# w47_LED_RGB_pinout.net
KiCad netlist of a schematic drawn in Altium Designer
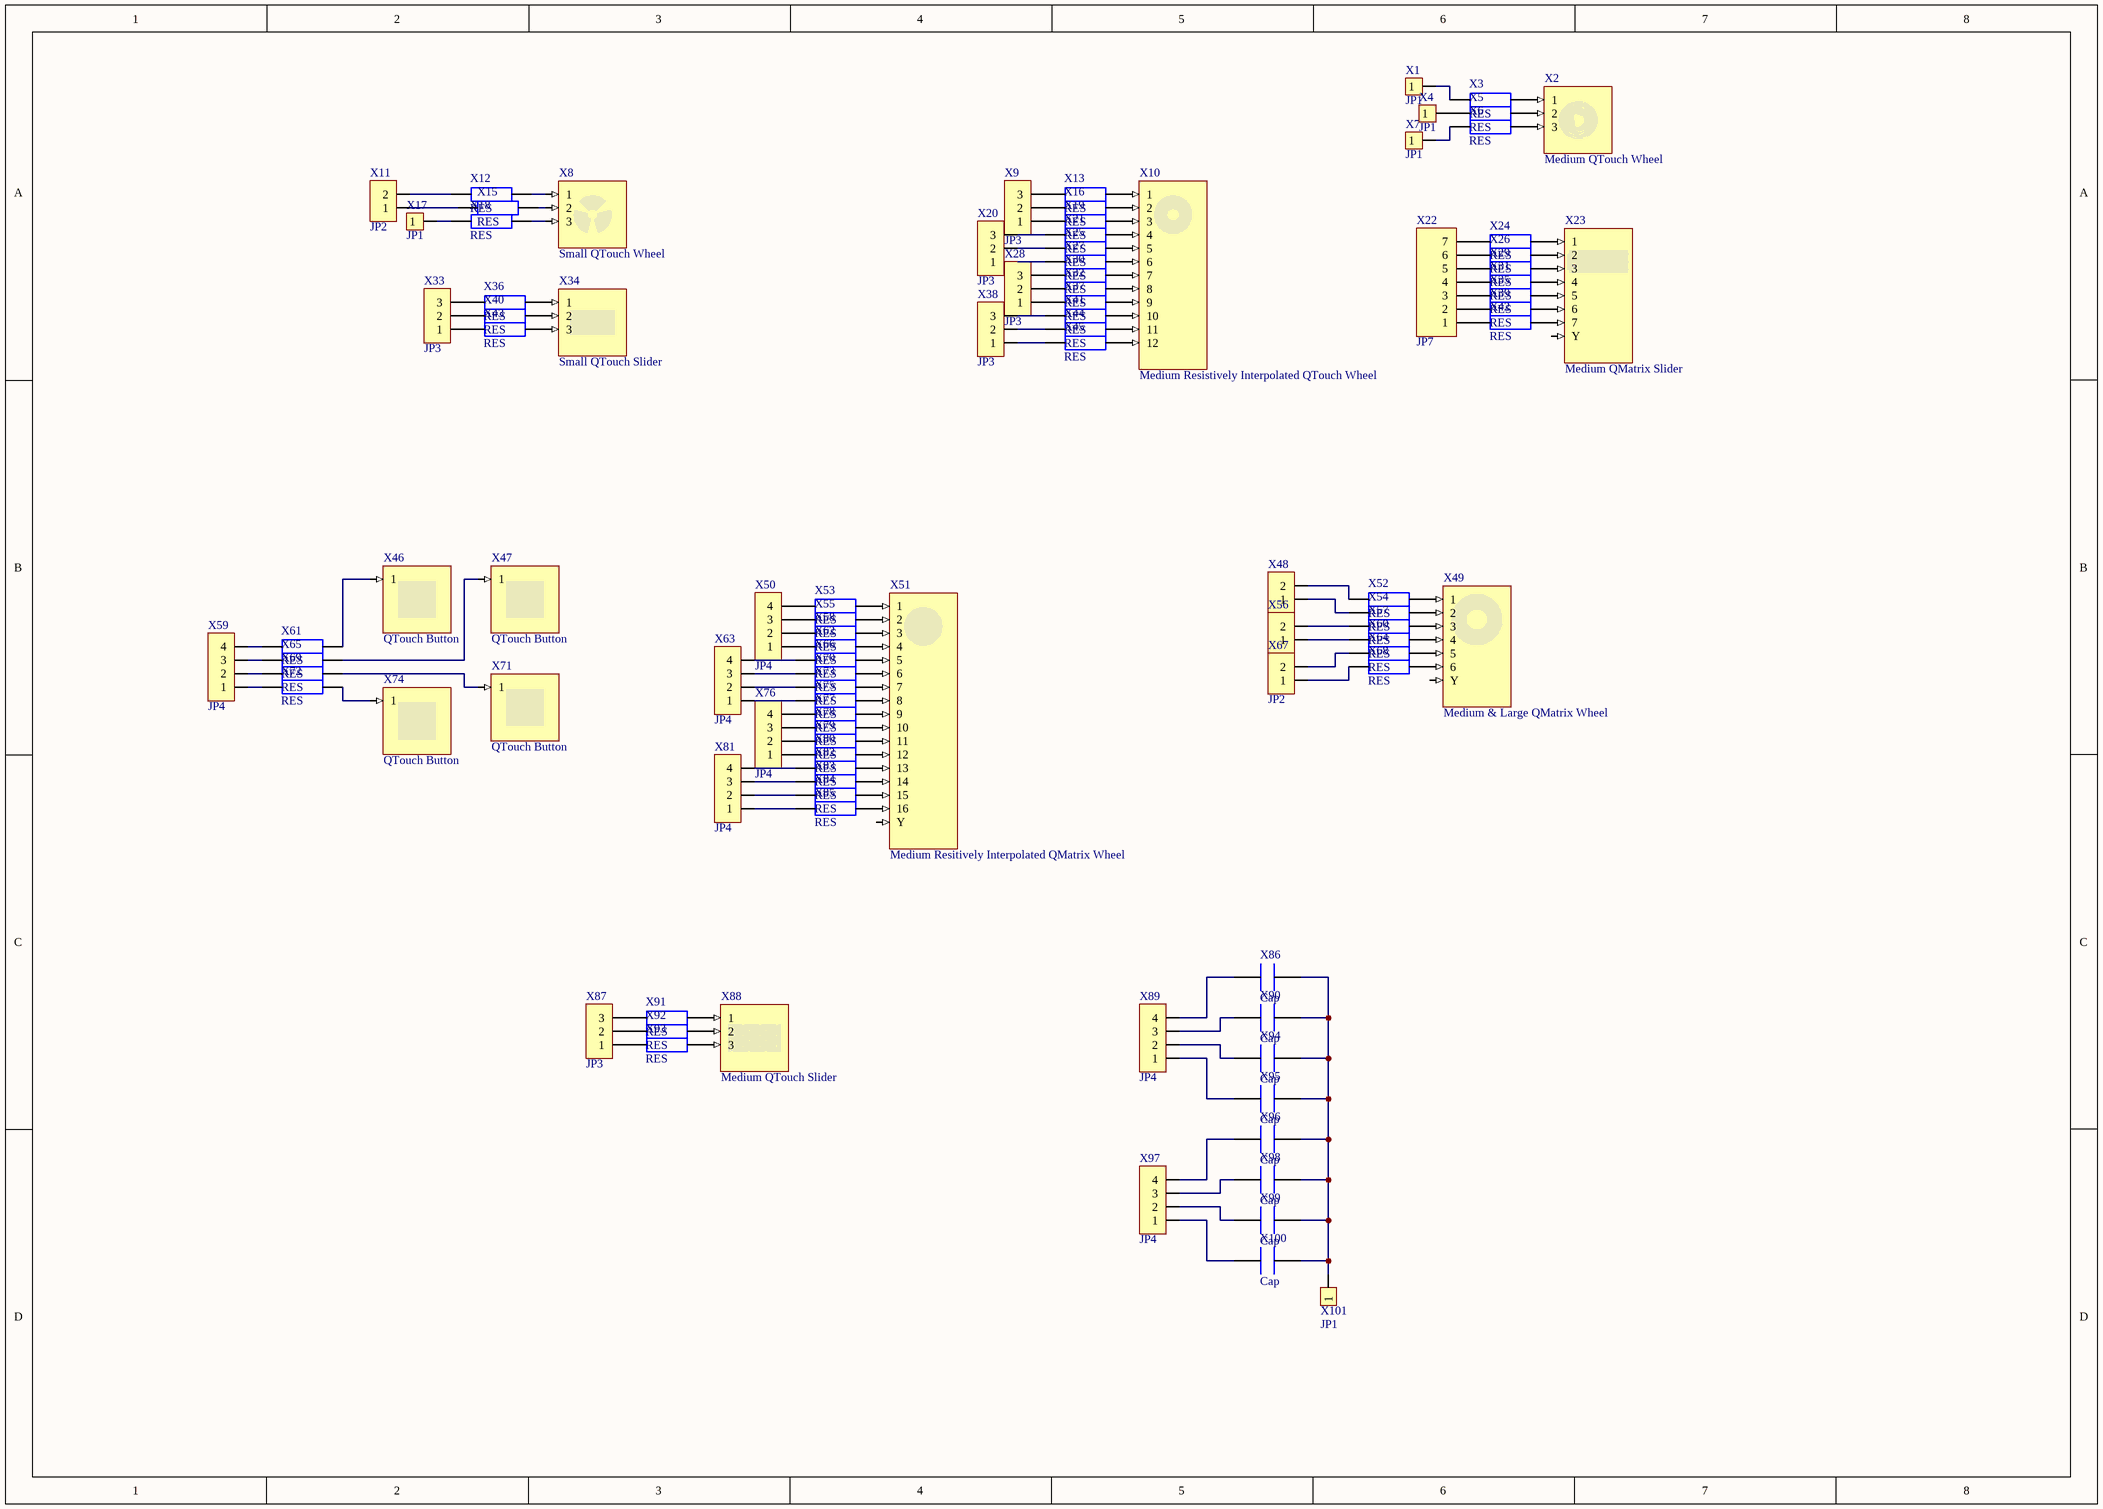
[diagram p0: w47_LED_RGB_pinout.SchDoc]

(export (version "E")
  (design (tool "Eeschema 10.0.6"))
  (components
    (comp (ref "X1")
      (value "JP1")
      (footprint "JP1-D1T")
      (description "WR-PHD 2.54 mm Angled Socket Header")
      (fields
        (field (name "MANUFACTURER") "Würth Elektronik eiSos GmbH")
        (field (name "PARTNO") "613002143121")
        (field (name "CREATED BY") "Karrer Zheng")
      )
      (libsource (lib "LIBRARY") (part "JP1"))
    )
    (comp (ref "X2")
      (value "Medium QTouch Wheel")
      (libsource (lib "Atmel QTouch") (part "MediumQTouchWheel"))
    )
    (comp (ref "X3")
      (value "RES")
      (footprint "RES")
      (description "điện trở size nhỏ")
      (libsource (lib "LuongTanDat") (part "RES"))
    )
    (comp (ref "X4")
      (value "JP1")
      (footprint "JP1-D1T")
      (description "WR-PHD 2.54 mm Angled Socket Header")
      (fields
        (field (name "MANUFACTURER") "Würth Elektronik eiSos GmbH")
        (field (name "PARTNO") "613002143121")
        (field (name "CREATED BY") "Karrer Zheng")
      )
      (libsource (lib "LIBRARY") (part "JP1"))
    )
    (comp (ref "X5")
      (value "RES")
      (footprint "RES")
      (description "điện trở size nhỏ")
      (libsource (lib "LuongTanDat") (part "RES"))
    )
    (comp (ref "X6")
      (value "RES")
      (footprint "RES")
      (description "điện trở size nhỏ")
      (libsource (lib "LuongTanDat") (part "RES"))
    )
    (comp (ref "X7")
      (value "JP1")
      (footprint "JP1-D1T")
      (description "WR-PHD 2.54 mm Angled Socket Header")
      (fields
        (field (name "MANUFACTURER") "Würth Elektronik eiSos GmbH")
        (field (name "PARTNO") "613002143121")
        (field (name "CREATED BY") "Karrer Zheng")
      )
      (libsource (lib "LIBRARY") (part "JP1"))
    )
    (comp (ref "X8") (value "Small QTouch Wheel") (libsource (lib "Atmel QTouch") (part "SmallQTouchWheel")))
    (comp (ref "X9")
      (value "JP3")
      (footprint "JP3-C1T")
      (description "WR-PHD 2.54 mm Angled Socket Header")
      (fields
        (field (name "MANUFACTURER") "Würth Elektronik eiSos GmbH")
        (field (name "PARTNO") "613003143121")
        (field (name "CREATED BY") "Karrer Zheng")
      )
      (libsource (lib "LIBRARY") (part "JP3"))
    )
    (comp (ref "X10")
      (value "Medium Resistively Interpolated QTouch Wheel")
      (libsource (lib "Atmel QTouch") (part "MediumResQTouchWheel"))
    )
    (comp (ref "X11")
      (value "JP2")
      (footprint "JP2-C1T")
      (description "WR-PHD 2.54 mm Angled Socket Header")
      (fields
        (field (name "MANUFACTURER") "Würth Elektronik eiSos GmbH")
        (field (name "PARTNO") "613002143121")
        (field (name "CREATED BY") "Karrer Zheng")
      )
      (libsource (lib "LIBRARY") (part "JP2"))
    )
    (comp (ref "X12")
      (value "RES")
      (footprint "RES")
      (description "điện trở size nhỏ")
      (libsource (lib "LuongTanDat") (part "RES"))
    )
    (comp (ref "X13")
      (value "RES")
      (footprint "RES")
      (description "điện trở size nhỏ")
      (libsource (lib "LuongTanDat") (part "RES"))
    )
    (comp (ref "X15")
      (value "RES")
      (footprint "RES")
      (description "điện trở size nhỏ")
      (libsource (lib "LuongTanDat") (part "RES"))
    )
    (comp (ref "X16")
      (value "RES")
      (footprint "RES")
      (description "điện trở size nhỏ")
      (libsource (lib "LuongTanDat") (part "RES"))
    )
    (comp (ref "X17")
      (value "JP1")
      (footprint "JP1-D1T")
      (description "WR-PHD 2.54 mm Angled Socket Header")
      (fields
        (field (name "MANUFACTURER") "Würth Elektronik eiSos GmbH")
        (field (name "PARTNO") "613002143121")
        (field (name "CREATED BY") "Karrer Zheng")
      )
      (libsource (lib "LIBRARY") (part "JP1"))
    )
    (comp (ref "X18")
      (value "RES")
      (footprint "RES")
      (description "điện trở size nhỏ")
      (libsource (lib "LuongTanDat") (part "RES"))
    )
    (comp (ref "X19")
      (value "RES")
      (footprint "RES")
      (description "điện trở size nhỏ")
      (libsource (lib "LuongTanDat") (part "RES"))
    )
    (comp (ref "X20")
      (value "JP3")
      (footprint "JP3-C1T")
      (description "WR-PHD 2.54 mm Angled Socket Header")
      (fields
        (field (name "MANUFACTURER") "Würth Elektronik eiSos GmbH")
        (field (name "PARTNO") "613003143121")
        (field (name "CREATED BY") "Karrer Zheng")
      )
      (libsource (lib "LIBRARY") (part "JP3"))
    )
    (comp (ref "X21")
      (value "RES")
      (footprint "RES")
      (description "điện trở size nhỏ")
      (libsource (lib "LuongTanDat") (part "RES"))
    )
    (comp (ref "X22")
      (value "JP7")
      (footprint "JP7-D1T")
      (description "WR-PHD 2.54 mm Angled Socket Header")
      (fields
        (field (name "MANUFACTURER") "Würth Elektronik eiSos GmbH")
        (field (name "PARTNO") "613007143121")
        (field (name "CREATED BY") "Karrer Zheng")
      )
      (libsource (lib "LIBRARY") (part "JP7"))
    )
    (comp (ref "X23")
      (value "Medium QMatrix Slider")
      (libsource (lib "Atmel QTouch") (part "MediumQMatrixSlider"))
    )
    (comp (ref "X24")
      (value "RES")
      (footprint "RES")
      (description "điện trở size nhỏ")
      (libsource (lib "LuongTanDat") (part "RES"))
    )
    (comp (ref "X25")
      (value "RES")
      (footprint "RES")
      (description "điện trở size nhỏ")
      (libsource (lib "LuongTanDat") (part "RES"))
    )
    (comp (ref "X26")
      (value "RES")
      (footprint "RES")
      (description "điện trở size nhỏ")
      (libsource (lib "LuongTanDat") (part "RES"))
    )
    (comp (ref "X27")
      (value "RES")
      (footprint "RES")
      (description "điện trở size nhỏ")
      (libsource (lib "LuongTanDat") (part "RES"))
    )
    (comp (ref "X28")
      (value "JP3")
      (footprint "JP3-C1T")
      (description "WR-PHD 2.54 mm Angled Socket Header")
      (fields
        (field (name "MANUFACTURER") "Würth Elektronik eiSos GmbH")
        (field (name "PARTNO") "613003143121")
        (field (name "CREATED BY") "Karrer Zheng")
      )
      (libsource (lib "LIBRARY") (part "JP3"))
    )
    (comp (ref "X29")
      (value "RES")
      (footprint "RES")
      (description "điện trở size nhỏ")
      (libsource (lib "LuongTanDat") (part "RES"))
    )
    (comp (ref "X30")
      (value "RES")
      (footprint "RES")
      (description "điện trở size nhỏ")
      (libsource (lib "LuongTanDat") (part "RES"))
    )
    (comp (ref "X31")
      (value "RES")
      (footprint "RES")
      (description "điện trở size nhỏ")
      (libsource (lib "LuongTanDat") (part "RES"))
    )
    (comp (ref "X32")
      (value "RES")
      (footprint "RES")
      (description "điện trở size nhỏ")
      (libsource (lib "LuongTanDat") (part "RES"))
    )
    (comp (ref "X33")
      (value "JP3")
      (footprint "JP3-C1T")
      (description "WR-PHD 2.54 mm Angled Socket Header")
      (fields
        (field (name "MANUFACTURER") "Würth Elektronik eiSos GmbH")
        (field (name "PARTNO") "613003143121")
        (field (name "CREATED BY") "Karrer Zheng")
      )
      (libsource (lib "LIBRARY") (part "JP3"))
    )
    (comp (ref "X34")
      (value "Small QTouch Slider")
      (libsource (lib "Atmel QTouch") (part "SmallQTouchSlider"))
    )
    (comp (ref "X35")
      (value "RES")
      (footprint "RES")
      (description "điện trở size nhỏ")
      (libsource (lib "LuongTanDat") (part "RES"))
    )
    (comp (ref "X36")
      (value "RES")
      (footprint "RES")
      (description "điện trở size nhỏ")
      (libsource (lib "LuongTanDat") (part "RES"))
    )
    (comp (ref "X37")
      (value "RES")
      (footprint "RES")
      (description "điện trở size nhỏ")
      (libsource (lib "LuongTanDat") (part "RES"))
    )
    (comp (ref "X38")
      (value "JP3")
      (footprint "JP3-C1T")
      (description "WR-PHD 2.54 mm Angled Socket Header")
      (fields
        (field (name "MANUFACTURER") "Würth Elektronik eiSos GmbH")
        (field (name "PARTNO") "613003143121")
        (field (name "CREATED BY") "Karrer Zheng")
      )
      (libsource (lib "LIBRARY") (part "JP3"))
    )
    (comp (ref "X39")
      (value "RES")
      (footprint "RES")
      (description "điện trở size nhỏ")
      (libsource (lib "LuongTanDat") (part "RES"))
    )
    (comp (ref "X40")
      (value "RES")
      (footprint "RES")
      (description "điện trở size nhỏ")
      (libsource (lib "LuongTanDat") (part "RES"))
    )
    (comp (ref "X41")
      (value "RES")
      (footprint "RES")
      (description "điện trở size nhỏ")
      (libsource (lib "LuongTanDat") (part "RES"))
    )
    (comp (ref "X42")
      (value "RES")
      (footprint "RES")
      (description "điện trở size nhỏ")
      (libsource (lib "LuongTanDat") (part "RES"))
    )
    (comp (ref "X43")
      (value "RES")
      (footprint "RES")
      (description "điện trở size nhỏ")
      (libsource (lib "LuongTanDat") (part "RES"))
    )
    (comp (ref "X44")
      (value "RES")
      (footprint "RES")
      (description "điện trở size nhỏ")
      (libsource (lib "LuongTanDat") (part "RES"))
    )
    (comp (ref "X45")
      (value "RES")
      (footprint "RES")
      (description "điện trở size nhỏ")
      (libsource (lib "LuongTanDat") (part "RES"))
    )
    (comp (ref "X46") (value "QTouch Button") (libsource (lib "Atmel QTouch") (part "QTouchButton")))
    (comp (ref "X47") (value "QTouch Button") (libsource (lib "Atmel QTouch") (part "QTouchButton")))
    (comp (ref "X48")
      (value "JP2")
      (footprint "JP2-C1T")
      (description "WR-PHD 2.54 mm Angled Socket Header")
      (fields
        (field (name "MANUFACTURER") "Würth Elektronik eiSos GmbH")
        (field (name "PARTNO") "613002143121")
        (field (name "CREATED BY") "Karrer Zheng")
      )
      (libsource (lib "LIBRARY") (part "JP2"))
    )
    (comp (ref "X49")
      (value "Medium & Large QMatrix Wheel")
      (libsource (lib "Atmel QTouch") (part "MediumLargeQMatrixWheel"))
    )
    (comp (ref "X50")
      (value "JP4")
      (footprint "JP4-C1T")
      (description "WR-PHD 2.54 mm Angled Socket Header")
      (fields
        (field (name "MANUFACTURER") "Würth Elektronik eiSos GmbH")
        (field (name "PARTNO") "613004143121")
        (field (name "CREATED BY") "Karrer Zheng")
      )
      (libsource (lib "LIBRARY") (part "JP4"))
    )
    (comp (ref "X51")
      (value "Medium Resitively Interpolated QMatrix Wheel")
      (libsource (lib "Atmel QTouch") (part "MediumResQMatrixWheel"))
    )
    (comp (ref "X52")
      (value "RES")
      (footprint "RES")
      (description "điện trở size nhỏ")
      (libsource (lib "LuongTanDat") (part "RES"))
    )
    (comp (ref "X53")
      (value "RES")
      (footprint "RES")
      (description "điện trở size nhỏ")
      (libsource (lib "LuongTanDat") (part "RES"))
    )
    (comp (ref "X54")
      (value "RES")
      (footprint "RES")
      (description "điện trở size nhỏ")
      (libsource (lib "LuongTanDat") (part "RES"))
    )
    (comp (ref "X55")
      (value "RES")
      (footprint "RES")
      (description "điện trở size nhỏ")
      (libsource (lib "LuongTanDat") (part "RES"))
    )
    (comp (ref "X56")
      (value "JP2")
      (footprint "JP2-C1T")
      (description "WR-PHD 2.54 mm Angled Socket Header")
      (fields
        (field (name "MANUFACTURER") "Würth Elektronik eiSos GmbH")
        (field (name "PARTNO") "613002143121")
        (field (name "CREATED BY") "Karrer Zheng")
      )
      (libsource (lib "LIBRARY") (part "JP2"))
    )
    (comp (ref "X57")
      (value "RES")
      (footprint "RES")
      (description "điện trở size nhỏ")
      (libsource (lib "LuongTanDat") (part "RES"))
    )
    (comp (ref "X58")
      (value "RES")
      (footprint "RES")
      (description "điện trở size nhỏ")
      (libsource (lib "LuongTanDat") (part "RES"))
    )
    (comp (ref "X59")
      (value "JP4")
      (footprint "JP4-C1T")
      (description "WR-PHD 2.54 mm Angled Socket Header")
      (fields
        (field (name "MANUFACTURER") "Würth Elektronik eiSos GmbH")
        (field (name "PARTNO") "613004143121")
        (field (name "CREATED BY") "Karrer Zheng")
      )
      (libsource (lib "LIBRARY") (part "JP4"))
    )
    (comp (ref "X60")
      (value "RES")
      (footprint "RES")
      (description "điện trở size nhỏ")
      (libsource (lib "LuongTanDat") (part "RES"))
    )
    (comp (ref "X61")
      (value "RES")
      (footprint "RES")
      (description "điện trở size nhỏ")
      (libsource (lib "LuongTanDat") (part "RES"))
    )
    (comp (ref "X62")
      (value "RES")
      (footprint "RES")
      (description "điện trở size nhỏ")
      (libsource (lib "LuongTanDat") (part "RES"))
    )
    (comp (ref "X63")
      (value "JP4")
      (footprint "JP4-C1T")
      (description "WR-PHD 2.54 mm Angled Socket Header")
      (fields
        (field (name "MANUFACTURER") "Würth Elektronik eiSos GmbH")
        (field (name "PARTNO") "613004143121")
        (field (name "CREATED BY") "Karrer Zheng")
      )
      (libsource (lib "LIBRARY") (part "JP4"))
    )
    (comp (ref "X64")
      (value "RES")
      (footprint "RES")
      (description "điện trở size nhỏ")
      (libsource (lib "LuongTanDat") (part "RES"))
    )
    (comp (ref "X65")
      (value "RES")
      (footprint "RES")
      (description "điện trở size nhỏ")
      (libsource (lib "LuongTanDat") (part "RES"))
    )
    (comp (ref "X66")
      (value "RES")
      (footprint "RES")
      (description "điện trở size nhỏ")
      (libsource (lib "LuongTanDat") (part "RES"))
    )
    (comp (ref "X67")
      (value "JP2")
      (footprint "JP2-C1T")
      (description "WR-PHD 2.54 mm Angled Socket Header")
      (fields
        (field (name "MANUFACTURER") "Würth Elektronik eiSos GmbH")
        (field (name "PARTNO") "613002143121")
        (field (name "CREATED BY") "Karrer Zheng")
      )
      (libsource (lib "LIBRARY") (part "JP2"))
    )
    (comp (ref "X68")
      (value "RES")
      (footprint "RES")
      (description "điện trở size nhỏ")
      (libsource (lib "LuongTanDat") (part "RES"))
    )
    (comp (ref "X69")
      (value "RES")
      (footprint "RES")
      (description "điện trở size nhỏ")
      (libsource (lib "LuongTanDat") (part "RES"))
    )
    (comp (ref "X70")
      (value "RES")
      (footprint "RES")
      (description "điện trở size nhỏ")
      (libsource (lib "LuongTanDat") (part "RES"))
    )
    (comp (ref "X71") (value "QTouch Button") (libsource (lib "Atmel QTouch") (part "QTouchButton")))
    (comp (ref "X72")
      (value "RES")
      (footprint "RES")
      (description "điện trở size nhỏ")
      (libsource (lib "LuongTanDat") (part "RES"))
    )
    (comp (ref "X73")
      (value "RES")
      (footprint "RES")
      (description "điện trở size nhỏ")
      (libsource (lib "LuongTanDat") (part "RES"))
    )
    (comp (ref "X74") (value "QTouch Button") (libsource (lib "Atmel QTouch") (part "QTouchButton")))
    (comp (ref "X75")
      (value "RES")
      (footprint "RES")
      (description "điện trở size nhỏ")
      (libsource (lib "LuongTanDat") (part "RES"))
    )
    (comp (ref "X76")
      (value "JP4")
      (footprint "JP4-C1T")
      (description "WR-PHD 2.54 mm Angled Socket Header")
      (fields
        (field (name "MANUFACTURER") "Würth Elektronik eiSos GmbH")
        (field (name "PARTNO") "613004143121")
        (field (name "CREATED BY") "Karrer Zheng")
      )
      (libsource (lib "LIBRARY") (part "JP4"))
    )
    (comp (ref "X77")
      (value "RES")
      (footprint "RES")
      (description "điện trở size nhỏ")
      (libsource (lib "LuongTanDat") (part "RES"))
    )
    (comp (ref "X78")
      (value "RES")
      (footprint "RES")
      (description "điện trở size nhỏ")
      (libsource (lib "LuongTanDat") (part "RES"))
    )
    (comp (ref "X79")
      (value "RES")
      (footprint "RES")
      (description "điện trở size nhỏ")
      (libsource (lib "LuongTanDat") (part "RES"))
    )
    (comp (ref "X80")
      (value "RES")
      (footprint "RES")
      (description "điện trở size nhỏ")
      (libsource (lib "LuongTanDat") (part "RES"))
    )
    (comp (ref "X81")
      (value "JP4")
      (footprint "JP4-C1T")
      (description "WR-PHD 2.54 mm Angled Socket Header")
      (fields
        (field (name "MANUFACTURER") "Würth Elektronik eiSos GmbH")
        (field (name "PARTNO") "613004143121")
        (field (name "CREATED BY") "Karrer Zheng")
      )
      (libsource (lib "LIBRARY") (part "JP4"))
    )
    (comp (ref "X82")
      (value "RES")
      (footprint "RES")
      (description "điện trở size nhỏ")
      (libsource (lib "LuongTanDat") (part "RES"))
    )
    (comp (ref "X83")
      (value "RES")
      (footprint "RES")
      (description "điện trở size nhỏ")
      (libsource (lib "LuongTanDat") (part "RES"))
    )
    (comp (ref "X84")
      (value "RES")
      (footprint "RES")
      (description "điện trở size nhỏ")
      (libsource (lib "LuongTanDat") (part "RES"))
    )
    (comp (ref "X85")
      (value "RES")
      (footprint "RES")
      (description "điện trở size nhỏ")
      (libsource (lib "LuongTanDat") (part "RES"))
    )
    (comp (ref "X86") (value "Cap") (footprint "CAP_2") (libsource (lib "LuongTanDat") (part "Cap")))
    (comp (ref "X87")
      (value "JP3")
      (footprint "JP3-C1T")
      (description "WR-PHD 2.54 mm Angled Socket Header")
      (fields
        (field (name "MANUFACTURER") "Würth Elektronik eiSos GmbH")
        (field (name "PARTNO") "613003143121")
        (field (name "CREATED BY") "Karrer Zheng")
      )
      (libsource (lib "LIBRARY") (part "JP3"))
    )
    (comp (ref "X88")
      (value "Medium QTouch Slider")
      (libsource (lib "Atmel QTouch") (part "MediumQTouchSlider"))
    )
    (comp (ref "X89")
      (value "JP4")
      (footprint "JP4-C1T")
      (description "WR-PHD 2.54 mm Angled Socket Header")
      (fields
        (field (name "MANUFACTURER") "Würth Elektronik eiSos GmbH")
        (field (name "PARTNO") "613004143121")
        (field (name "CREATED BY") "Karrer Zheng")
      )
      (libsource (lib "LIBRARY") (part "JP4"))
    )
    (comp (ref "X90") (value "Cap") (footprint "CAP_2") (libsource (lib "LuongTanDat") (part "Cap")))
    (comp (ref "X91")
      (value "RES")
      (footprint "RES")
      (description "điện trở size nhỏ")
      (libsource (lib "LuongTanDat") (part "RES"))
    )
    (comp (ref "X92")
      (value "RES")
      (footprint "RES")
      (description "điện trở size nhỏ")
      (libsource (lib "LuongTanDat") (part "RES"))
    )
    (comp (ref "X93")
      (value "RES")
      (footprint "RES")
      (description "điện trở size nhỏ")
      (libsource (lib "LuongTanDat") (part "RES"))
    )
    (comp (ref "X94") (value "Cap") (footprint "CAP_2") (libsource (lib "LuongTanDat") (part "Cap")))
    (comp (ref "X95") (value "Cap") (footprint "CAP_2") (libsource (lib "LuongTanDat") (part "Cap")))
    (comp (ref "X96") (value "Cap") (footprint "CAP_2") (libsource (lib "LuongTanDat") (part "Cap")))
    (comp (ref "X97")
      (value "JP4")
      (footprint "JP4-C1T")
      (description "WR-PHD 2.54 mm Angled Socket Header")
      (fields
        (field (name "MANUFACTURER") "Würth Elektronik eiSos GmbH")
        (field (name "PARTNO") "613004143121")
        (field (name "CREATED BY") "Karrer Zheng")
      )
      (libsource (lib "LIBRARY") (part "JP4"))
    )
    (comp (ref "X98") (value "Cap") (footprint "CAP_2") (libsource (lib "LuongTanDat") (part "Cap")))
    (comp (ref "X99") (value "Cap") (footprint "CAP_2") (libsource (lib "LuongTanDat") (part "Cap")))
    (comp (ref "X100") (value "Cap") (footprint "CAP_2") (libsource (lib "LuongTanDat") (part "Cap")))
    (comp (ref "X101")
      (value "JP1")
      (footprint "JP1-D1T")
      (description "WR-PHD 2.54 mm Angled Socket Header")
      (fields
        (field (name "MANUFACTURER") "Würth Elektronik eiSos GmbH")
        (field (name "PARTNO") "613002143121")
        (field (name "CREATED BY") "Karrer Zheng")
      )
      (libsource (lib "") (part "JP1_1"))
    )
  )
  (nets
    (net (code "1") (name "Net-(X1-Pad1)") (class "Default")
      (node (ref "X1") (pin "1") (pinfunction "1_1") (pintype "passive"))
      (node (ref "X3") (pin "1") (pinfunction "1_1") (pintype "passive"))
    )
    (net (code "2") (name "Net-(X2-Pad1)") (class "Default")
      (node (ref "X2") (pin "1") (pinfunction "1_1") (pintype "input"))
      (node (ref "X3") (pin "2") (pinfunction "2_2") (pintype "passive"))
    )
    (net (code "3") (name "Net-(X2-Pad2)") (class "Default")
      (node (ref "X2") (pin "2") (pinfunction "2_2") (pintype "input"))
      (node (ref "X5") (pin "2") (pinfunction "2_2") (pintype "passive"))
    )
    (net (code "4") (name "Net-(X2-Pad3)") (class "Default")
      (node (ref "X2") (pin "3") (pinfunction "3_3") (pintype "input"))
      (node (ref "X6") (pin "2") (pinfunction "2_2") (pintype "passive"))
    )
    (net (code "5") (name "Net-(X4-Pad1)") (class "Default")
      (node (ref "X4") (pin "1") (pinfunction "1_1") (pintype "passive"))
      (node (ref "X5") (pin "1") (pinfunction "1_1") (pintype "passive"))
    )
    (net (code "6") (name "Net-(X6-Pad1)") (class "Default")
      (node (ref "X6") (pin "1") (pinfunction "1_1") (pintype "passive"))
      (node (ref "X7") (pin "1") (pinfunction "1_1") (pintype "passive"))
    )
    (net (code "7") (name "Net-(X10-Pad1)") (class "Default")
      (node (ref "X10") (pin "1") (pinfunction "1_1") (pintype "input"))
      (node (ref "X13") (pin "2") (pinfunction "2_2") (pintype "passive"))
    )
    (net (code "8") (name "Net-(X10-Pad2)") (class "Default")
      (node (ref "X10") (pin "2") (pinfunction "2_2") (pintype "input"))
      (node (ref "X16") (pin "2") (pinfunction "2_2") (pintype "passive"))
    )
    (net (code "9") (name "Net-(X10-Pad3)") (class "Default")
      (node (ref "X10") (pin "3") (pinfunction "3_3") (pintype "input"))
      (node (ref "X19") (pin "2") (pinfunction "2_2") (pintype "passive"))
    )
    (net (code "10") (name "Net-(X10-Pad4)") (class "Default")
      (node (ref "X10") (pin "4") (pinfunction "4_4") (pintype "input"))
      (node (ref "X21") (pin "2") (pinfunction "2_2") (pintype "passive"))
    )
    (net (code "11") (name "Net-(X10-Pad5)") (class "Default")
      (node (ref "X10") (pin "5") (pinfunction "5_5") (pintype "input"))
      (node (ref "X25") (pin "2") (pinfunction "2_2") (pintype "passive"))
    )
    (net (code "12") (name "Net-(X10-Pad6)") (class "Default")
      (node (ref "X10") (pin "6") (pinfunction "6_6") (pintype "input"))
      (node (ref "X27") (pin "2") (pinfunction "2_2") (pintype "passive"))
    )
    (net (code "13") (name "Net-(X10-Pad7)") (class "Default")
      (node (ref "X10") (pin "7") (pinfunction "7_7") (pintype "input"))
      (node (ref "X30") (pin "2") (pinfunction "2_2") (pintype "passive"))
    )
    (net (code "14") (name "Net-(X10-Pad8)") (class "Default")
      (node (ref "X10") (pin "8") (pinfunction "8_8") (pintype "input"))
      (node (ref "X32") (pin "2") (pinfunction "2_2") (pintype "passive"))
    )
    (net (code "15") (name "Net-(X10-Pad9)") (class "Default")
      (node (ref "X10") (pin "9") (pinfunction "9_9") (pintype "input"))
      (node (ref "X37") (pin "2") (pinfunction "2_2") (pintype "passive"))
    )
    (net (code "16") (name "Net-(X10-Pad10)") (class "Default")
      (node (ref "X10") (pin "10") (pinfunction "10_10") (pintype "input"))
      (node (ref "X41") (pin "2") (pinfunction "2_2") (pintype "passive"))
    )
    (net (code "17") (name "Net-(X10-Pad11)") (class "Default")
      (node (ref "X10") (pin "11") (pinfunction "11_11") (pintype "input"))
      (node (ref "X44") (pin "2") (pinfunction "2_2") (pintype "passive"))
    )
    (net (code "18") (name "Net-(X10-Pad12)") (class "Default")
      (node (ref "X10") (pin "12") (pinfunction "12_12") (pintype "input"))
      (node (ref "X45") (pin "2") (pinfunction "2_2") (pintype "passive"))
    )
    (net (code "19") (name "Net-(X11-Pad1)") (class "Default")
      (node (ref "X11") (pin "1") (pinfunction "1_1") (pintype "passive"))
      (node (ref "X15") (pin "1") (pinfunction "1_1") (pintype "passive"))
    )
    (net (code "20") (name "Net-(X11-Pad2)") (class "Default")
      (node (ref "X11") (pin "2") (pinfunction "2_2") (pintype "passive"))
      (node (ref "X12") (pin "1") (pinfunction "1_1") (pintype "passive"))
    )
    (net (code "21") (name "Net-(X12-Pad2)") (class "Default")
      (node (ref "X12") (pin "2") (pinfunction "2_2") (pintype "passive"))
      (node (ref "X8") (pin "1") (pinfunction "1_1") (pintype "input"))
    )
    (net (code "22") (name "Net-(X13-Pad1)") (class "Default")
      (node (ref "X13") (pin "1") (pinfunction "1_1") (pintype "passive"))
      (node (ref "X9") (pin "3") (pinfunction "3_3") (pintype "passive"))
    )
    (net (code "23") (name "Net-(X15-Pad2)") (class "Default")
      (node (ref "X15") (pin "2") (pinfunction "2_2") (pintype "passive"))
      (node (ref "X8") (pin "2") (pinfunction "2_2") (pintype "input"))
    )
    (net (code "24") (name "Net-(X16-Pad1)") (class "Default")
      (node (ref "X16") (pin "1") (pinfunction "1_1") (pintype "passive"))
      (node (ref "X9") (pin "2") (pinfunction "2_2") (pintype "passive"))
    )
    (net (code "25") (name "Net-(X17-Pad1)") (class "Default")
      (node (ref "X17") (pin "1") (pinfunction "1_1") (pintype "passive"))
      (node (ref "X18") (pin "1") (pinfunction "1_1") (pintype "passive"))
    )
    (net (code "26") (name "Net-(X18-Pad2)") (class "Default")
      (node (ref "X18") (pin "2") (pinfunction "2_2") (pintype "passive"))
      (node (ref "X8") (pin "3") (pinfunction "3_3") (pintype "input"))
    )
    (net (code "27") (name "Net-(X19-Pad1)") (class "Default")
      (node (ref "X19") (pin "1") (pinfunction "1_1") (pintype "passive"))
      (node (ref "X9") (pin "1") (pinfunction "1_1") (pintype "passive"))
    )
    (net (code "28") (name "Net-(X20-Pad1)") (class "Default")
      (node (ref "X20") (pin "1") (pinfunction "1_1") (pintype "passive"))
      (node (ref "X27") (pin "1") (pinfunction "1_1") (pintype "passive"))
    )
    (net (code "29") (name "Net-(X20-Pad2)") (class "Default")
      (node (ref "X20") (pin "2") (pinfunction "2_2") (pintype "passive"))
      (node (ref "X25") (pin "1") (pinfunction "1_1") (pintype "passive"))
    )
    (net (code "30") (name "Net-(X20-Pad3)") (class "Default")
      (node (ref "X20") (pin "3") (pinfunction "3_3") (pintype "passive"))
      (node (ref "X21") (pin "1") (pinfunction "1_1") (pintype "passive"))
    )
    (net (code "31") (name "Net-(X22-Pad1)") (class "Default")
      (node (ref "X22") (pin "1") (pinfunction "1_1") (pintype "passive"))
      (node (ref "X42") (pin "1") (pinfunction "1_1") (pintype "passive"))
    )
    (net (code "32") (name "Net-(X22-Pad2)") (class "Default")
      (node (ref "X22") (pin "2") (pinfunction "2_2") (pintype "passive"))
      (node (ref "X39") (pin "1") (pinfunction "1_1") (pintype "passive"))
    )
    (net (code "33") (name "Net-(X22-Pad3)") (class "Default")
      (node (ref "X22") (pin "3") (pinfunction "3_3") (pintype "passive"))
      (node (ref "X35") (pin "1") (pinfunction "1_1") (pintype "passive"))
    )
    (net (code "34") (name "Net-(X22-Pad4)") (class "Default")
      (node (ref "X22") (pin "4") (pinfunction "4_4") (pintype "passive"))
      (node (ref "X31") (pin "1") (pinfunction "1_1") (pintype "passive"))
    )
    (net (code "35") (name "Net-(X22-Pad5)") (class "Default")
      (node (ref "X22") (pin "5") (pinfunction "5_5") (pintype "passive"))
      (node (ref "X29") (pin "1") (pinfunction "1_1") (pintype "passive"))
    )
    (net (code "36") (name "Net-(X22-Pad6)") (class "Default")
      (node (ref "X22") (pin "6") (pinfunction "6_6") (pintype "passive"))
      (node (ref "X26") (pin "1") (pinfunction "1_1") (pintype "passive"))
    )
    (net (code "37") (name "Net-(X22-Pad7)") (class "Default")
      (node (ref "X22") (pin "7") (pinfunction "7_7") (pintype "passive"))
      (node (ref "X24") (pin "1") (pinfunction "1_1") (pintype "passive"))
    )
    (net (code "38") (name "Net-(X23-Pad1)") (class "Default")
      (node (ref "X23") (pin "1") (pinfunction "1_1") (pintype "input"))
      (node (ref "X24") (pin "2") (pinfunction "2_2") (pintype "passive"))
    )
    (net (code "39") (name "Net-(X23-Pad2)") (class "Default")
      (node (ref "X23") (pin "2") (pinfunction "2_2") (pintype "input"))
      (node (ref "X26") (pin "2") (pinfunction "2_2") (pintype "passive"))
    )
    (net (code "40") (name "Net-(X23-Pad3)") (class "Default")
      (node (ref "X23") (pin "3") (pinfunction "3_3") (pintype "input"))
      (node (ref "X29") (pin "2") (pinfunction "2_2") (pintype "passive"))
    )
    (net (code "41") (name "Net-(X23-Pad4)") (class "Default")
      (node (ref "X23") (pin "4") (pinfunction "4_4") (pintype "input"))
      (node (ref "X31") (pin "2") (pinfunction "2_2") (pintype "passive"))
    )
    (net (code "42") (name "Net-(X23-Pad5)") (class "Default")
      (node (ref "X23") (pin "5") (pinfunction "5_5") (pintype "input"))
      (node (ref "X35") (pin "2") (pinfunction "2_2") (pintype "passive"))
    )
    (net (code "43") (name "Net-(X23-Pad6)") (class "Default")
      (node (ref "X23") (pin "6") (pinfunction "6_6") (pintype "input"))
      (node (ref "X39") (pin "2") (pinfunction "2_2") (pintype "passive"))
    )
    (net (code "44") (name "Net-(X23-Pad7)") (class "Default")
      (node (ref "X23") (pin "7") (pinfunction "7_7") (pintype "input"))
      (node (ref "X42") (pin "2") (pinfunction "2_2") (pintype "passive"))
    )
    (net (code "45") (name "Net-(X28-Pad1)") (class "Default")
      (node (ref "X28") (pin "1") (pinfunction "1_1") (pintype "passive"))
      (node (ref "X37") (pin "1") (pinfunction "1_1") (pintype "passive"))
    )
    (net (code "46") (name "Net-(X28-Pad2)") (class "Default")
      (node (ref "X28") (pin "2") (pinfunction "2_2") (pintype "passive"))
      (node (ref "X32") (pin "1") (pinfunction "1_1") (pintype "passive"))
    )
    (net (code "47") (name "Net-(X28-Pad3)") (class "Default")
      (node (ref "X28") (pin "3") (pinfunction "3_3") (pintype "passive"))
      (node (ref "X30") (pin "1") (pinfunction "1_1") (pintype "passive"))
    )
    (net (code "48") (name "Net-(X33-Pad1)") (class "Default")
      (node (ref "X33") (pin "1") (pinfunction "1_1") (pintype "passive"))
      (node (ref "X43") (pin "1") (pinfunction "1_1") (pintype "passive"))
    )
    (net (code "49") (name "Net-(X33-Pad2)") (class "Default")
      (node (ref "X33") (pin "2") (pinfunction "2_2") (pintype "passive"))
      (node (ref "X40") (pin "1") (pinfunction "1_1") (pintype "passive"))
    )
    (net (code "50") (name "Net-(X33-Pad3)") (class "Default")
      (node (ref "X33") (pin "3") (pinfunction "3_3") (pintype "passive"))
      (node (ref "X36") (pin "1") (pinfunction "1_1") (pintype "passive"))
    )
    (net (code "51") (name "Net-(X34-Pad1)") (class "Default")
      (node (ref "X34") (pin "1") (pinfunction "1_1") (pintype "input"))
      (node (ref "X36") (pin "2") (pinfunction "2_2") (pintype "passive"))
    )
    (net (code "52") (name "Net-(X34-Pad2)") (class "Default")
      (node (ref "X34") (pin "2") (pinfunction "2_2") (pintype "input"))
      (node (ref "X40") (pin "2") (pinfunction "2_2") (pintype "passive"))
    )
    (net (code "53") (name "Net-(X34-Pad3)") (class "Default")
      (node (ref "X34") (pin "3") (pinfunction "3_3") (pintype "input"))
      (node (ref "X43") (pin "2") (pinfunction "2_2") (pintype "passive"))
    )
    (net (code "54") (name "Net-(X38-Pad1)") (class "Default")
      (node (ref "X38") (pin "1") (pinfunction "1_1") (pintype "passive"))
      (node (ref "X45") (pin "1") (pinfunction "1_1") (pintype "passive"))
    )
    (net (code "55") (name "Net-(X38-Pad2)") (class "Default")
      (node (ref "X38") (pin "2") (pinfunction "2_2") (pintype "passive"))
      (node (ref "X44") (pin "1") (pinfunction "1_1") (pintype "passive"))
    )
    (net (code "56") (name "Net-(X38-Pad3)") (class "Default")
      (node (ref "X38") (pin "3") (pinfunction "3_3") (pintype "passive"))
      (node (ref "X41") (pin "1") (pinfunction "1_1") (pintype "passive"))
    )
    (net (code "57") (name "Net-(X46-Pad1)") (class "Default")
      (node (ref "X46") (pin "1") (pinfunction "1_1") (pintype "input"))
      (node (ref "X61") (pin "2") (pinfunction "2_2") (pintype "passive"))
    )
    (net (code "58") (name "Net-(X47-Pad1)") (class "Default")
      (node (ref "X47") (pin "1") (pinfunction "1_1") (pintype "input"))
      (node (ref "X65") (pin "2") (pinfunction "2_2") (pintype "passive"))
    )
    (net (code "59") (name "Net-(X48-Pad1)") (class "Default")
      (node (ref "X48") (pin "1") (pinfunction "1_1") (pintype "passive"))
      (node (ref "X54") (pin "1") (pinfunction "1_1") (pintype "passive"))
    )
    (net (code "60") (name "Net-(X48-Pad2)") (class "Default")
      (node (ref "X48") (pin "2") (pinfunction "2_2") (pintype "passive"))
      (node (ref "X52") (pin "1") (pinfunction "1_1") (pintype "passive"))
    )
    (net (code "61") (name "Net-(X49-Pad1)") (class "Default")
      (node (ref "X49") (pin "1") (pinfunction "1_1") (pintype "input"))
      (node (ref "X52") (pin "2") (pinfunction "2_2") (pintype "passive"))
    )
    (net (code "62") (name "Net-(X49-Pad2)") (class "Default")
      (node (ref "X49") (pin "2") (pinfunction "2_2") (pintype "input"))
      (node (ref "X54") (pin "2") (pinfunction "2_2") (pintype "passive"))
    )
    (net (code "63") (name "Net-(X49-Pad3)") (class "Default")
      (node (ref "X49") (pin "3") (pinfunction "3_3") (pintype "input"))
      (node (ref "X57") (pin "2") (pinfunction "2_2") (pintype "passive"))
    )
    (net (code "64") (name "Net-(X49-Pad4)") (class "Default")
      (node (ref "X49") (pin "4") (pinfunction "4_4") (pintype "input"))
      (node (ref "X60") (pin "2") (pinfunction "2_2") (pintype "passive"))
    )
    (net (code "65") (name "Net-(X49-Pad5)") (class "Default")
      (node (ref "X49") (pin "5") (pinfunction "5_5") (pintype "input"))
      (node (ref "X64") (pin "2") (pinfunction "2_2") (pintype "passive"))
    )
    (net (code "66") (name "Net-(X49-Pad6)") (class "Default")
      (node (ref "X49") (pin "6") (pinfunction "6_6") (pintype "input"))
      (node (ref "X68") (pin "2") (pinfunction "2_2") (pintype "passive"))
    )
    (net (code "67") (name "Net-(X50-Pad1)") (class "Default")
      (node (ref "X50") (pin "1") (pinfunction "1_1") (pintype "passive"))
      (node (ref "X62") (pin "1") (pinfunction "1_1") (pintype "passive"))
    )
    (net (code "68") (name "Net-(X50-Pad2)") (class "Default")
      (node (ref "X50") (pin "2") (pinfunction "2_2") (pintype "passive"))
      (node (ref "X58") (pin "1") (pinfunction "1_1") (pintype "passive"))
    )
    (net (code "69") (name "Net-(X50-Pad3)") (class "Default")
      (node (ref "X50") (pin "3") (pinfunction "3_3") (pintype "passive"))
      (node (ref "X55") (pin "1") (pinfunction "1_1") (pintype "passive"))
    )
    (net (code "70") (name "Net-(X50-Pad4)") (class "Default")
      (node (ref "X50") (pin "4") (pinfunction "4_4") (pintype "passive"))
      (node (ref "X53") (pin "1") (pinfunction "1_1") (pintype "passive"))
    )
    (net (code "71") (name "Net-(X51-Pad1)") (class "Default")
      (node (ref "X51") (pin "1") (pinfunction "1_1") (pintype "input"))
      (node (ref "X53") (pin "2") (pinfunction "2_2") (pintype "passive"))
    )
    (net (code "72") (name "Net-(X51-Pad2)") (class "Default")
      (node (ref "X51") (pin "2") (pinfunction "2_2") (pintype "input"))
      (node (ref "X55") (pin "2") (pinfunction "2_2") (pintype "passive"))
    )
    (net (code "73") (name "Net-(X51-Pad3)") (class "Default")
      (node (ref "X51") (pin "3") (pinfunction "3_3") (pintype "input"))
      (node (ref "X58") (pin "2") (pinfunction "2_2") (pintype "passive"))
    )
    (net (code "74") (name "Net-(X51-Pad4)") (class "Default")
      (node (ref "X51") (pin "4") (pinfunction "4_4") (pintype "input"))
      (node (ref "X62") (pin "2") (pinfunction "2_2") (pintype "passive"))
    )
    (net (code "75") (name "Net-(X51-Pad5)") (class "Default")
      (node (ref "X51") (pin "5") (pinfunction "5_5") (pintype "input"))
      (node (ref "X66") (pin "2") (pinfunction "2_2") (pintype "passive"))
    )
    (net (code "76") (name "Net-(X51-Pad6)") (class "Default")
      (node (ref "X51") (pin "6") (pinfunction "6_6") (pintype "input"))
      (node (ref "X70") (pin "2") (pinfunction "2_2") (pintype "passive"))
    )
    (net (code "77") (name "Net-(X51-Pad7)") (class "Default")
      (node (ref "X51") (pin "7") (pinfunction "7_7") (pintype "input"))
      (node (ref "X73") (pin "2") (pinfunction "2_2") (pintype "passive"))
    )
    (net (code "78") (name "Net-(X51-Pad8)") (class "Default")
      (node (ref "X51") (pin "8") (pinfunction "8_8") (pintype "input"))
      (node (ref "X75") (pin "2") (pinfunction "2_2") (pintype "passive"))
    )
    (net (code "79") (name "Net-(X51-Pad9)") (class "Default")
      (node (ref "X51") (pin "9") (pinfunction "9_9") (pintype "input"))
      (node (ref "X77") (pin "2") (pinfunction "2_2") (pintype "passive"))
    )
    (net (code "80") (name "Net-(X51-Pad10)") (class "Default")
      (node (ref "X51") (pin "10") (pinfunction "10_10") (pintype "input"))
      (node (ref "X78") (pin "2") (pinfunction "2_2") (pintype "passive"))
    )
    (net (code "81") (name "Net-(X51-Pad11)") (class "Default")
      (node (ref "X51") (pin "11") (pinfunction "11_11") (pintype "input"))
      (node (ref "X79") (pin "2") (pinfunction "2_2") (pintype "passive"))
    )
    (net (code "82") (name "Net-(X51-Pad12)") (class "Default")
      (node (ref "X51") (pin "12") (pinfunction "12_12") (pintype "input"))
      (node (ref "X80") (pin "2") (pinfunction "2_2") (pintype "passive"))
    )
    (net (code "83") (name "Net-(X51-Pad13)") (class "Default")
      (node (ref "X51") (pin "13") (pinfunction "13_13") (pintype "input"))
      (node (ref "X82") (pin "2") (pinfunction "2_2") (pintype "passive"))
    )
    (net (code "84") (name "Net-(X51-Pad14)") (class "Default")
      (node (ref "X51") (pin "14") (pinfunction "14_14") (pintype "input"))
      (node (ref "X83") (pin "2") (pinfunction "2_2") (pintype "passive"))
    )
    (net (code "85") (name "Net-(X51-Pad15)") (class "Default")
      (node (ref "X51") (pin "15") (pinfunction "15_15") (pintype "input"))
      (node (ref "X84") (pin "2") (pinfunction "2_2") (pintype "passive"))
    )
    (net (code "86") (name "Net-(X51-Pad16)") (class "Default")
      (node (ref "X51") (pin "16") (pinfunction "16_16") (pintype "input"))
      (node (ref "X85") (pin "2") (pinfunction "2_2") (pintype "passive"))
    )
    (net (code "87") (name "Net-(X56-Pad1)") (class "Default")
      (node (ref "X56") (pin "1") (pinfunction "1_1") (pintype "passive"))
      (node (ref "X60") (pin "1") (pinfunction "1_1") (pintype "passive"))
    )
    (net (code "88") (name "Net-(X56-Pad2)") (class "Default")
      (node (ref "X56") (pin "2") (pinfunction "2_2") (pintype "passive"))
      (node (ref "X57") (pin "1") (pinfunction "1_1") (pintype "passive"))
    )
    (net (code "89") (name "Net-(X59-Pad1)") (class "Default")
      (node (ref "X59") (pin "1") (pinfunction "1_1") (pintype "passive"))
      (node (ref "X72") (pin "1") (pinfunction "1_1") (pintype "passive"))
    )
    (net (code "90") (name "Net-(X59-Pad2)") (class "Default")
      (node (ref "X59") (pin "2") (pinfunction "2_2") (pintype "passive"))
      (node (ref "X69") (pin "1") (pinfunction "1_1") (pintype "passive"))
    )
    (net (code "91") (name "Net-(X59-Pad3)") (class "Default")
      (node (ref "X59") (pin "3") (pinfunction "3_3") (pintype "passive"))
      (node (ref "X65") (pin "1") (pinfunction "1_1") (pintype "passive"))
    )
    (net (code "92") (name "Net-(X59-Pad4)") (class "Default")
      (node (ref "X59") (pin "4") (pinfunction "4_4") (pintype "passive"))
      (node (ref "X61") (pin "1") (pinfunction "1_1") (pintype "passive"))
    )
    (net (code "93") (name "Net-(X63-Pad1)") (class "Default")
      (node (ref "X63") (pin "1") (pinfunction "1_1") (pintype "passive"))
      (node (ref "X75") (pin "1") (pinfunction "1_1") (pintype "passive"))
    )
    (net (code "94") (name "Net-(X63-Pad2)") (class "Default")
      (node (ref "X63") (pin "2") (pinfunction "2_2") (pintype "passive"))
      (node (ref "X73") (pin "1") (pinfunction "1_1") (pintype "passive"))
    )
    (net (code "95") (name "Net-(X63-Pad3)") (class "Default")
      (node (ref "X63") (pin "3") (pinfunction "3_3") (pintype "passive"))
      (node (ref "X70") (pin "1") (pinfunction "1_1") (pintype "passive"))
    )
    (net (code "96") (name "Net-(X63-Pad4)") (class "Default")
      (node (ref "X63") (pin "4") (pinfunction "4_4") (pintype "passive"))
      (node (ref "X66") (pin "1") (pinfunction "1_1") (pintype "passive"))
    )
    (net (code "97") (name "Net-(X64-Pad1)") (class "Default")
      (node (ref "X64") (pin "1") (pinfunction "1_1") (pintype "passive"))
      (node (ref "X67") (pin "2") (pinfunction "2_2") (pintype "passive"))
    )
    (net (code "98") (name "Net-(X67-Pad1)") (class "Default")
      (node (ref "X67") (pin "1") (pinfunction "1_1") (pintype "passive"))
      (node (ref "X68") (pin "1") (pinfunction "1_1") (pintype "passive"))
    )
    (net (code "99") (name "Net-(X69-Pad2)") (class "Default")
      (node (ref "X69") (pin "2") (pinfunction "2_2") (pintype "passive"))
      (node (ref "X71") (pin "1") (pinfunction "1_1") (pintype "input"))
    )
    (net (code "100") (name "Net-(X72-Pad2)") (class "Default")
      (node (ref "X72") (pin "2") (pinfunction "2_2") (pintype "passive"))
      (node (ref "X74") (pin "1") (pinfunction "1_1") (pintype "input"))
    )
    (net (code "101") (name "Net-(X76-Pad1)") (class "Default")
      (node (ref "X76") (pin "1") (pinfunction "1_1") (pintype "passive"))
      (node (ref "X80") (pin "1") (pinfunction "1_1") (pintype "passive"))
    )
    (net (code "102") (name "Net-(X76-Pad2)") (class "Default")
      (node (ref "X76") (pin "2") (pinfunction "2_2") (pintype "passive"))
      (node (ref "X79") (pin "1") (pinfunction "1_1") (pintype "passive"))
    )
    (net (code "103") (name "Net-(X76-Pad3)") (class "Default")
      (node (ref "X76") (pin "3") (pinfunction "3_3") (pintype "passive"))
      (node (ref "X78") (pin "1") (pinfunction "1_1") (pintype "passive"))
    )
    (net (code "104") (name "Net-(X76-Pad4)") (class "Default")
      (node (ref "X76") (pin "4") (pinfunction "4_4") (pintype "passive"))
      (node (ref "X77") (pin "1") (pinfunction "1_1") (pintype "passive"))
    )
    (net (code "105") (name "Net-(X81-Pad1)") (class "Default")
      (node (ref "X81") (pin "1") (pinfunction "1_1") (pintype "passive"))
      (node (ref "X85") (pin "1") (pinfunction "1_1") (pintype "passive"))
    )
    (net (code "106") (name "Net-(X81-Pad2)") (class "Default")
      (node (ref "X81") (pin "2") (pinfunction "2_2") (pintype "passive"))
      (node (ref "X84") (pin "1") (pinfunction "1_1") (pintype "passive"))
    )
    (net (code "107") (name "Net-(X81-Pad3)") (class "Default")
      (node (ref "X81") (pin "3") (pinfunction "3_3") (pintype "passive"))
      (node (ref "X83") (pin "1") (pinfunction "1_1") (pintype "passive"))
    )
    (net (code "108") (name "Net-(X81-Pad4)") (class "Default")
      (node (ref "X81") (pin "4") (pinfunction "4_4") (pintype "passive"))
      (node (ref "X82") (pin "1") (pinfunction "1_1") (pintype "passive"))
    )
    (net (code "109") (name "Net-(X86-Pad1)") (class "Default")
      (node (ref "X86") (pin "1") (pinfunction "1_1") (pintype "passive"))
      (node (ref "X89") (pin "4") (pinfunction "4_4") (pintype "passive"))
    )
    (net (code "110") (name "Net-(X87-Pad1)") (class "Default")
      (node (ref "X87") (pin "1") (pinfunction "1_1") (pintype "passive"))
      (node (ref "X93") (pin "1") (pinfunction "1_1") (pintype "passive"))
    )
    (net (code "111") (name "Net-(X87-Pad2)") (class "Default")
      (node (ref "X87") (pin "2") (pinfunction "2_2") (pintype "passive"))
      (node (ref "X92") (pin "1") (pinfunction "1_1") (pintype "passive"))
    )
    (net (code "112") (name "Net-(X87-Pad3)") (class "Default")
      (node (ref "X87") (pin "3") (pinfunction "3_3") (pintype "passive"))
      (node (ref "X91") (pin "1") (pinfunction "1_1") (pintype "passive"))
    )
    (net (code "113") (name "Net-(X88-Pad1)") (class "Default")
      (node (ref "X88") (pin "1") (pinfunction "1_1") (pintype "input"))
      (node (ref "X91") (pin "2") (pinfunction "2_2") (pintype "passive"))
    )
    (net (code "114") (name "Net-(X88-Pad2)") (class "Default")
      (node (ref "X88") (pin "2") (pinfunction "2_2") (pintype "input"))
      (node (ref "X92") (pin "2") (pinfunction "2_2") (pintype "passive"))
    )
    (net (code "115") (name "Net-(X88-Pad3)") (class "Default")
      (node (ref "X88") (pin "3") (pinfunction "3_3") (pintype "input"))
      (node (ref "X93") (pin "2") (pinfunction "2_2") (pintype "passive"))
    )
    (net (code "116") (name "Net-(X89-Pad1)") (class "Default")
      (node (ref "X89") (pin "1") (pinfunction "1_1") (pintype "passive"))
      (node (ref "X95") (pin "1") (pinfunction "1_1") (pintype "passive"))
    )
    (net (code "117") (name "Net-(X89-Pad2)") (class "Default")
      (node (ref "X89") (pin "2") (pinfunction "2_2") (pintype "passive"))
      (node (ref "X94") (pin "1") (pinfunction "1_1") (pintype "passive"))
    )
    (net (code "118") (name "Net-(X89-Pad3)") (class "Default")
      (node (ref "X89") (pin "3") (pinfunction "3_3") (pintype "passive"))
      (node (ref "X90") (pin "1") (pinfunction "1_1") (pintype "passive"))
    )
    (net (code "119") (name "Net-(X96-Pad1)") (class "Default")
      (node (ref "X96") (pin "1") (pinfunction "1_1") (pintype "passive"))
      (node (ref "X97") (pin "4") (pinfunction "4_4") (pintype "passive"))
    )
    (net (code "120") (name "Net-(X97-Pad2)") (class "Default")
      (node (ref "X97") (pin "2") (pinfunction "2_2") (pintype "passive"))
      (node (ref "X99") (pin "1") (pinfunction "1_1") (pintype "passive"))
    )
    (net (code "121") (name "Net-(X97-Pad3)") (class "Default")
      (node (ref "X97") (pin "3") (pinfunction "3_3") (pintype "passive"))
      (node (ref "X98") (pin "1") (pinfunction "1_1") (pintype "passive"))
    )
    (net (code "122") (name "Net-(X100-Pad1)") (class "Default")
      (node (ref "X100") (pin "1") (pinfunction "1_1") (pintype "passive"))
      (node (ref "X97") (pin "1") (pinfunction "1_1") (pintype "passive"))
    )
    (net (code "123") (name "Net-(X100-Pad2)") (class "Default")
      (node (ref "X100") (pin "2") (pinfunction "2_2") (pintype "passive"))
      (node (ref "X101") (pin "1") (pinfunction "1_1") (pintype "passive"))
      (node (ref "X86") (pin "2") (pinfunction "2_2") (pintype "passive"))
      (node (ref "X90") (pin "2") (pinfunction "2_2") (pintype "passive"))
      (node (ref "X94") (pin "2") (pinfunction "2_2") (pintype "passive"))
      (node (ref "X95") (pin "2") (pinfunction "2_2") (pintype "passive"))
      (node (ref "X96") (pin "2") (pinfunction "2_2") (pintype "passive"))
      (node (ref "X98") (pin "2") (pinfunction "2_2") (pintype "passive"))
      (node (ref "X99") (pin "2") (pinfunction "2_2") (pintype "passive"))
    )
    (net (code "124") (name "unconnected-(X23-PadY)") (class "Default")
      (node (ref "X23") (pin "Y") (pinfunction "Y_Y") (pintype "input"))
    )
    (net (code "125") (name "unconnected-(X49-PadY)") (class "Default")
      (node (ref "X49") (pin "Y") (pinfunction "Y_Y") (pintype "input"))
    )
    (net (code "126") (name "unconnected-(X51-PadY)") (class "Default")
      (node (ref "X51") (pin "Y") (pinfunction "Y_Y") (pintype "input"))
    )
  )
)
